# game_console_schematic.net
KiCad netlist of a schematic drawn in Altium Designer
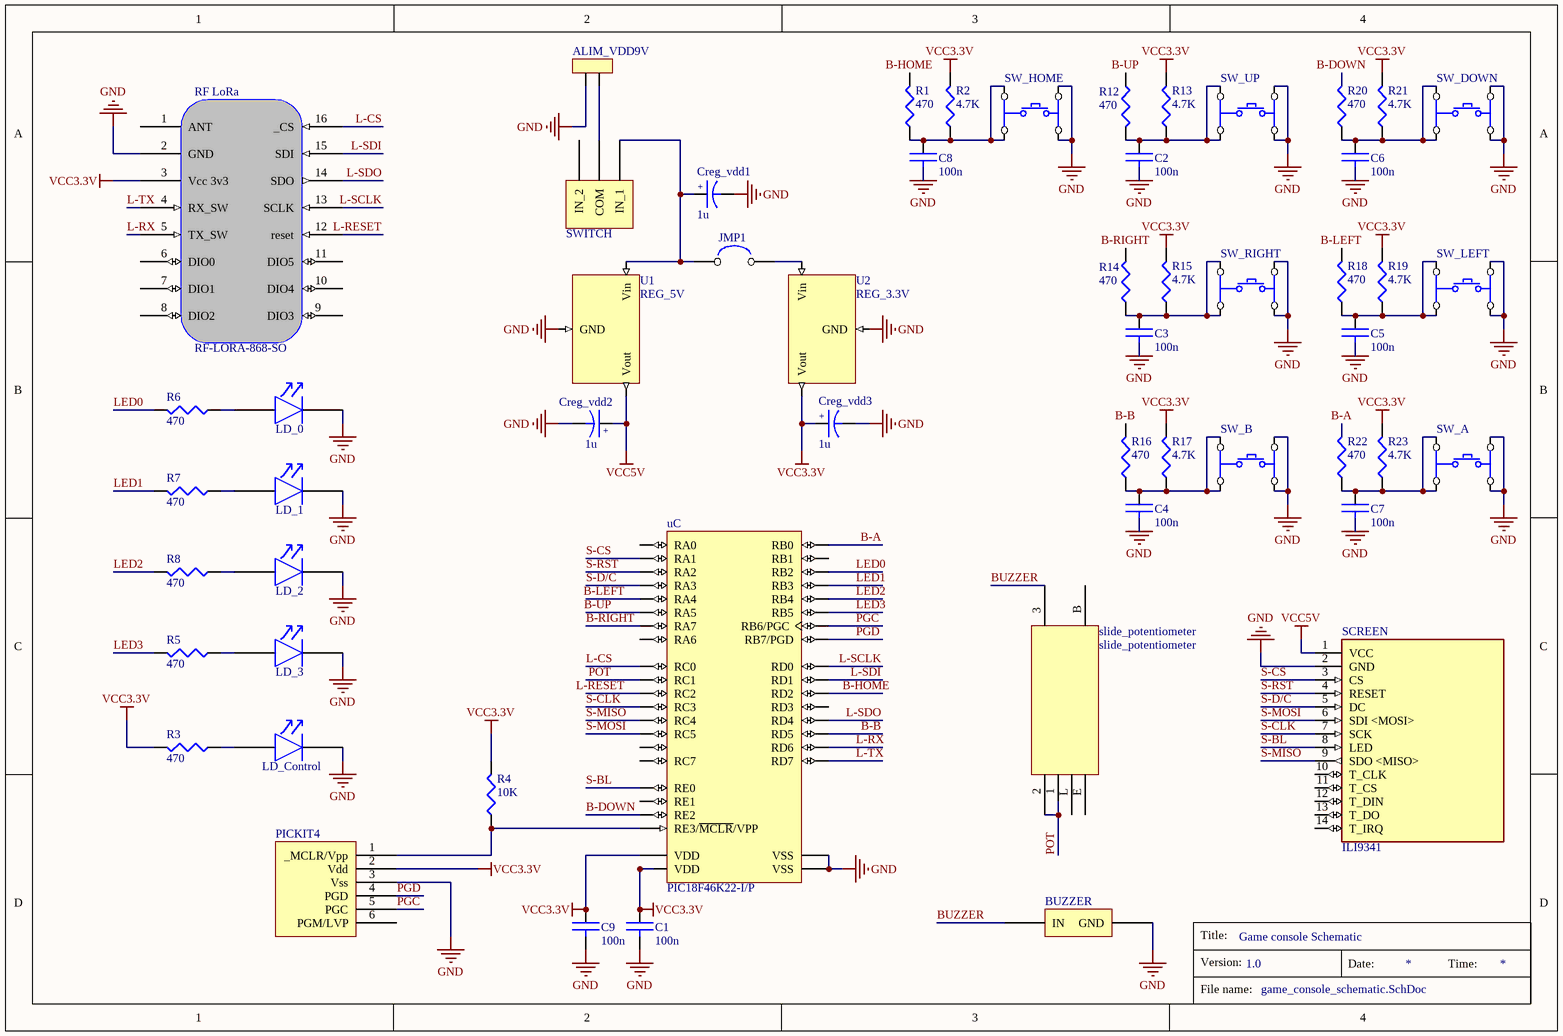
[diagram p0: game_console_schematic.SchDoc]

(export (version "E")
  (design (tool "Eeschema 10.0.6"))
  (components
    (comp (ref "ALIM_VDD9V")
      (value "ALIM_9V")
      (footprint "AMP_2")
      (description "connecteur alim 2 pôles")
      (libsource (lib "power2") (part "POWER2"))
    )
    (comp (ref "BUZZER") (value "BUZZER") (footprint "BUZZER") (libsource (lib "buzzer") (part "BUZZER")))
    (comp (ref "C1")
      (value "100n")
      (footprint "0805")
      (description "capacité non polarisée")
      (fields (field (name "Comment") "CAP"))
      (libsource (lib "ISEN_basics_15-02-2023") (part "CAP"))
    )
    (comp (ref "C2")
      (value "100n")
      (footprint "0805")
      (description "capacité non polarisée")
      (fields (field (name "Comment") "C"))
      (libsource (lib "ISEN_basics_15-02-2023") (part "CAP"))
    )
    (comp (ref "C3")
      (value "100n")
      (footprint "0805")
      (description "capacité non polarisée")
      (fields (field (name "Comment") "C"))
      (libsource (lib "ISEN_basics_15-02-2023") (part "CAP"))
    )
    (comp (ref "C4")
      (value "100n")
      (footprint "0805")
      (description "capacité non polarisée")
      (fields (field (name "Comment") "C"))
      (libsource (lib "ISEN_basics_15-02-2023") (part "CAP"))
    )
    (comp (ref "C5")
      (value "100n")
      (footprint "0805")
      (description "capacité non polarisée")
      (fields (field (name "Comment") "C"))
      (libsource (lib "ISEN_basics_15-02-2023") (part "CAP"))
    )
    (comp (ref "C6")
      (value "100n")
      (footprint "0805")
      (description "capacité non polarisée")
      (fields (field (name "Comment") "C"))
      (libsource (lib "ISEN_basics_15-02-2023") (part "CAP"))
    )
    (comp (ref "C7")
      (value "100n")
      (footprint "0805")
      (description "capacité non polarisée")
      (fields (field (name "Comment") "C"))
      (libsource (lib "ISEN_basics_15-02-2023") (part "CAP"))
    )
    (comp (ref "C8")
      (value "100n")
      (footprint "0805")
      (description "capacité non polarisée")
      (fields (field (name "Comment") "C"))
      (libsource (lib "ISEN_basics_15-02-2023") (part "CAP"))
    )
    (comp (ref "C9")
      (value "100n")
      (footprint "0805")
      (description "capacité non polarisée")
      (fields (field (name "Comment") "CAP"))
      (libsource (lib "ISEN_basics_15-02-2023") (part "CAP"))
    )
    (comp (ref "Creg_vdd1")
      (value "1u")
      (footprint "RB.2/.4")
      (description "capacité polarisée")
      (fields (field (name "Comment") "CAP_POL"))
      (libsource (lib "condensateur_pol") (part "CAP_POL"))
    )
    (comp (ref "Creg_vdd2")
      (value "1u")
      (footprint "RB.2/.4")
      (description "capacité polarisée")
      (fields (field (name "Comment") "CAP_POL"))
      (libsource (lib "condensateur_pol") (part "CAP_POL"))
    )
    (comp (ref "Creg_vdd3")
      (value "1u")
      (footprint "RB.2/.4")
      (description "capacité polarisée")
      (fields (field (name "Comment") "CAP_POL"))
      (libsource (lib "condensateur_pol") (part "CAP_POL"))
    )
    (comp (ref "JMP1")
      (value "JUMPER")
      (footprint "JMP2-100")
      (description "cavalier 1 position")
      (libsource (lib "jumper2") (part "JUMPER2"))
    )
    (comp (ref "LD_0")
      (value "0")
      (footprint "LED0805")
      (description "LED 5mm/3mm/CMS")
      (libsource (lib "led") (part "LED"))
    )
    (comp (ref "LD_1")
      (value "1")
      (footprint "LED0805")
      (description "LED 5mm/3mm/CMS")
      (libsource (lib "led") (part "LED"))
    )
    (comp (ref "LD_2")
      (value "2")
      (footprint "LED0805")
      (description "LED 5mm/3mm/CMS")
      (libsource (lib "led") (part "LED"))
    )
    (comp (ref "LD_3")
      (value "3")
      (footprint "LED0805")
      (description "LED 5mm/3mm/CMS")
      (libsource (lib "led") (part "LED"))
    )
    (comp (ref "LD_Control")
      (value "comment")
      (footprint "LED0805")
      (description "LED 5mm/3mm/CMS")
      (libsource (lib "led") (part "LED"))
    )
    (comp (ref "PICKIT4")
      (value "PIC-ICSP")
      (footprint "PIC-ICSP")
      (libsource (lib "pickit4-connection") (part "PIC-ICSP"))
    )
    (comp (ref "R1")
      (value "470")
      (footprint "0805")
      (description "resistance")
      (fields (field (name "Comment") "R0"))
      (libsource (lib "ISEN_basics_15-02-2023") (part "RES"))
    )
    (comp (ref "R2")
      (value "4.7K")
      (footprint "0805")
      (description "resistance")
      (fields (field (name "Comment") "RK"))
      (libsource (lib "ISEN_basics_15-02-2023") (part "RES"))
    )
    (comp (ref "R3")
      (value "470")
      (footprint "0805")
      (description "resistance")
      (fields (field (name "Comment") "R0"))
      (libsource (lib "ISEN_basics_15-02-2023") (part "RES"))
    )
    (comp (ref "R4")
      (value "10K")
      (footprint "0805")
      (description "resistance")
      (fields (field (name "Comment") "RES"))
      (libsource (lib "ISEN_basics_15-02-2023") (part "RES"))
    )
    (comp (ref "R5")
      (value "470")
      (footprint "0805")
      (description "resistance")
      (fields (field (name "Comment") "R0"))
      (libsource (lib "ISEN_basics_15-02-2023") (part "RES"))
    )
    (comp (ref "R6")
      (value "470")
      (footprint "0805")
      (description "resistance")
      (fields (field (name "Comment") "R0"))
      (libsource (lib "ISEN_basics_15-02-2023") (part "RES"))
    )
    (comp (ref "R7")
      (value "470")
      (footprint "0805")
      (description "resistance")
      (fields (field (name "Comment") "R0"))
      (libsource (lib "ISEN_basics_15-02-2023") (part "RES"))
    )
    (comp (ref "R8")
      (value "470")
      (footprint "0805")
      (description "resistance")
      (fields (field (name "Comment") "R0"))
      (libsource (lib "ISEN_basics_15-02-2023") (part "RES"))
    )
    (comp (ref "R12")
      (value "470")
      (footprint "0805")
      (description "resistance")
      (fields (field (name "Comment") "R0"))
      (libsource (lib "ISEN_basics_15-02-2023") (part "RES"))
    )
    (comp (ref "R13")
      (value "4.7K")
      (footprint "0805")
      (description "resistance")
      (fields (field (name "Comment") "RK"))
      (libsource (lib "ISEN_basics_15-02-2023") (part "RES"))
    )
    (comp (ref "R14")
      (value "470")
      (footprint "0805")
      (description "resistance")
      (fields (field (name "Comment") "R0"))
      (libsource (lib "ISEN_basics_15-02-2023") (part "RES"))
    )
    (comp (ref "R15")
      (value "4.7K")
      (footprint "0805")
      (description "resistance")
      (fields (field (name "Comment") "RK"))
      (libsource (lib "ISEN_basics_15-02-2023") (part "RES"))
    )
    (comp (ref "R16")
      (value "470")
      (footprint "0805")
      (description "resistance")
      (fields (field (name "Comment") "R0"))
      (libsource (lib "ISEN_basics_15-02-2023") (part "RES"))
    )
    (comp (ref "R17")
      (value "4.7K")
      (footprint "0805")
      (description "resistance")
      (fields (field (name "Comment") "RK"))
      (libsource (lib "ISEN_basics_15-02-2023") (part "RES"))
    )
    (comp (ref "R18")
      (value "470")
      (footprint "0805")
      (description "resistance")
      (fields (field (name "Comment") "R0"))
      (libsource (lib "ISEN_basics_15-02-2023") (part "RES"))
    )
    (comp (ref "R19")
      (value "4.7K")
      (footprint "0805")
      (description "resistance")
      (fields (field (name "Comment") "RK"))
      (libsource (lib "ISEN_basics_15-02-2023") (part "RES"))
    )
    (comp (ref "R20")
      (value "470")
      (footprint "0805")
      (description "resistance")
      (fields (field (name "Comment") "R0"))
      (libsource (lib "ISEN_basics_15-02-2023") (part "RES"))
    )
    (comp (ref "R21")
      (value "4.7K")
      (footprint "0805")
      (description "resistance")
      (fields (field (name "Comment") "RK"))
      (libsource (lib "ISEN_basics_15-02-2023") (part "RES"))
    )
    (comp (ref "R22")
      (value "470")
      (footprint "0805")
      (description "resistance")
      (fields (field (name "Comment") "R0"))
      (libsource (lib "ISEN_basics_15-02-2023") (part "RES"))
    )
    (comp (ref "R23")
      (value "4.7K")
      (footprint "0805")
      (description "resistance")
      (fields (field (name "Comment") "RK"))
      (libsource (lib "ISEN_basics_15-02-2023") (part "RES"))
    )
    (comp (ref "RF LoRa")
      (value "RF-LORA-868-SO")
      (footprint "RF-LORA-868-DIP")
      (libsource (lib "rf-lora") (part "RF-LORA-868-SO"))
    )
    (comp (ref "SCREEN")
      (value "ILI9341")
      (footprint "ILI9341_Display")
      (fields (field (name "MF") "Adafruit Industries") (field (name "MP") "2478"))
      (libsource (lib "ILI9341_Display") (part "2478"))
    )
    (comp (ref "slide_potentiometer")
      (value "slide_potentiometer")
      (footprint "ptl_series_slide_potentiometer")
      (libsource (lib "slide_potentiometer") (part "slide_potentiometer"))
    )
    (comp (ref "SWITCH")
      (value "SWITCH_SPDT_ON_ON_2")
      (footprint "SW_MFP-161")
      (libsource (lib "commutateur") (part "SWITCH_SPDT_ON_ON_2"))
    )
    (comp (ref "SW_A") (value "A") (footprint "KSA") (libsource (lib "custom_push_button") (part "SW_PB")))
    (comp (ref "SW_B") (value "B") (footprint "KSA") (libsource (lib "custom_push_button") (part "SW_PB")))
    (comp (ref "SW_DOWN")
      (value "SW_PB")
      (footprint "KSA")
      (libsource (lib "custom_push_button") (part "SW_PB"))
    )
    (comp (ref "SW_HOME")
      (value "HOME")
      (footprint "KSA")
      (libsource (lib "custom_push_button") (part "SW_PB"))
    )
    (comp (ref "SW_LEFT")
      (value "SW_PB")
      (footprint "KSA")
      (libsource (lib "custom_push_button") (part "SW_PB"))
    )
    (comp (ref "SW_RIGHT")
      (value "SW_PB")
      (footprint "KSA")
      (libsource (lib "custom_push_button") (part "SW_PB"))
    )
    (comp (ref "SW_UP")
      (value "SW_PB")
      (footprint "KSA")
      (libsource (lib "custom_push_button") (part "SW_PB"))
    )
    (comp (ref "U1")
      (value "REG_5V")
      (footprint "TO220H")
      (description "régulateur positif fixe")
      (libsource (lib "regulateur") (part "REG_POS"))
    )
    (comp (ref "U2")
      (value "REG_3.3V")
      (footprint "TO220H")
      (description "régulateur positif fixe")
      (libsource (lib "") (part "REG_POS_1"))
    )
    (comp (ref "uC")
      (value "PIC18F46K22-I/P")
      (footprint "MCHP-PDIP-P40")
      (fields (field (name "MANUFACTURER") "Microchip"))
      (libsource (lib "Microchip PIC18") (part "PIC18F46K22-I/P"))
    )
  )
  (nets
    (net (code "1") (name "/B-A") (class "Default")
      (node (ref "R22") (pin "2") (pintype "passive"))
      (node (ref "uC") (pin "33") (pinfunction "RB0_33") (pintype "bidirectional"))
    )
    (net (code "2") (name "/B-B") (class "Default")
      (node (ref "R16") (pin "2") (pintype "passive"))
      (node (ref "uC") (pin "28") (pinfunction "RD5_28") (pintype "bidirectional"))
    )
    (net (code "3") (name "/B-DOWN") (class "Default")
      (node (ref "R20") (pin "2") (pintype "passive"))
      (node (ref "uC") (pin "10") (pinfunction "RE2_10") (pintype "bidirectional"))
    )
    (net (code "4") (name "/B-HOME") (class "Default")
      (node (ref "R1") (pin "2") (pintype "passive"))
      (node (ref "uC") (pin "21") (pinfunction "RD2_21") (pintype "bidirectional"))
    )
    (net (code "5") (name "/B-LEFT") (class "Default")
      (node (ref "R18") (pin "2") (pintype "passive"))
      (node (ref "uC") (pin "6") (pinfunction "RA4_6") (pintype "bidirectional"))
    )
    (net (code "6") (name "/B-RIGHT") (class "Default")
      (node (ref "R14") (pin "2") (pintype "passive"))
      (node (ref "uC") (pin "13") (pinfunction "RA7_13") (pintype "bidirectional"))
    )
    (net (code "7") (name "/B-UP") (class "Default")
      (node (ref "R12") (pin "1") (pintype "passive"))
      (node (ref "uC") (pin "7") (pinfunction "RA5_7") (pintype "bidirectional"))
    )
    (net (code "8") (name "/BUZZER") (class "Default")
      (node (ref "BUZZER") (pin "1") (pinfunction "IN_1") (pintype "passive"))
      (node (ref "slide_potentiometer") (pin "3") (pintype "passive"))
    )
    (net (code "9") (name "/L-CS") (class "Default")
      (node (ref "RF LoRa") (pin "16") (pinfunction "_CS_16") (pintype "input"))
      (node (ref "uC") (pin "15") (pinfunction "RC0_15") (pintype "bidirectional"))
    )
    (net (code "10") (name "/L-RESET") (class "Default")
      (node (ref "RF LoRa") (pin "12") (pinfunction "reset_12") (pintype "input"))
      (node (ref "uC") (pin "17") (pinfunction "RC2_17") (pintype "bidirectional"))
    )
    (net (code "11") (name "/L-RX") (class "Default")
      (node (ref "RF LoRa") (pin "5") (pinfunction "TX_SW_5") (pintype "input"))
      (node (ref "uC") (pin "29") (pinfunction "RD6_29") (pintype "bidirectional"))
    )
    (net (code "12") (name "/L-SCLK") (class "Default")
      (node (ref "RF LoRa") (pin "13") (pinfunction "SCLK_13") (pintype "input"))
      (node (ref "uC") (pin "19") (pinfunction "RD0_19") (pintype "bidirectional"))
    )
    (net (code "13") (name "/L-SDI") (class "Default")
      (node (ref "RF LoRa") (pin "15") (pinfunction "SDI_15") (pintype "input"))
      (node (ref "uC") (pin "20") (pinfunction "RD1_20") (pintype "bidirectional"))
    )
    (net (code "14") (name "/L-SDO") (class "Default")
      (node (ref "RF LoRa") (pin "14") (pinfunction "SDO_14") (pintype "output"))
      (node (ref "uC") (pin "27") (pinfunction "RD4_27") (pintype "bidirectional"))
    )
    (net (code "15") (name "/L-TX") (class "Default")
      (node (ref "RF LoRa") (pin "4") (pinfunction "RX_SW_4") (pintype "input"))
      (node (ref "uC") (pin "30") (pinfunction "RD7_30") (pintype "bidirectional"))
    )
    (net (code "16") (name "/LED0") (class "Default")
      (node (ref "R6") (pin "2") (pintype "passive"))
      (node (ref "uC") (pin "35") (pinfunction "RB2_35") (pintype "bidirectional"))
    )
    (net (code "17") (name "/LED1") (class "Default")
      (node (ref "R7") (pin "2") (pintype "passive"))
      (node (ref "uC") (pin "36") (pinfunction "RB3_36") (pintype "bidirectional"))
    )
    (net (code "18") (name "/LED2") (class "Default")
      (node (ref "R8") (pin "2") (pintype "passive"))
      (node (ref "uC") (pin "37") (pinfunction "RB4_37") (pintype "bidirectional"))
    )
    (net (code "19") (name "/LED3") (class "Default")
      (node (ref "R5") (pin "2") (pintype "passive"))
      (node (ref "uC") (pin "38") (pinfunction "RB5_38") (pintype "bidirectional"))
    )
    (net (code "20") (name "/PGC") (class "Default")
      (node (ref "PICKIT4") (pin "5") (pinfunction "PGC_5") (pintype "passive"))
      (node (ref "uC") (pin "39") (pinfunction "RB6/PGC_39") (pintype "bidirectional"))
    )
    (net (code "21") (name "/PGD") (class "Default")
      (node (ref "PICKIT4") (pin "4") (pinfunction "PGD_4") (pintype "passive"))
      (node (ref "uC") (pin "40") (pinfunction "RB7/PGD_40") (pintype "bidirectional"))
    )
    (net (code "22") (name "/POT") (class "Default")
      (node (ref "slide_potentiometer") (pin "1") (pintype "passive"))
      (node (ref "slide_potentiometer") (pin "2") (pintype "passive"))
      (node (ref "uC") (pin "16") (pinfunction "RC1_16") (pintype "bidirectional"))
    )
    (net (code "23") (name "/S-BL") (class "Default")
      (node (ref "SCREEN") (pin "8") (pinfunction "LED_8") (pintype "input"))
      (node (ref "uC") (pin "8") (pinfunction "RE0_8") (pintype "bidirectional"))
    )
    (net (code "24") (name "/S-CLK") (class "Default")
      (node (ref "SCREEN") (pin "7") (pinfunction "SCK_7") (pintype "input"))
      (node (ref "uC") (pin "18") (pinfunction "RC3_18") (pintype "bidirectional"))
    )
    (net (code "25") (name "/S-CS") (class "Default")
      (node (ref "SCREEN") (pin "3") (pinfunction "CS_3") (pintype "input"))
      (node (ref "uC") (pin "3") (pinfunction "RA1_3") (pintype "bidirectional"))
    )
    (net (code "26") (name "/S-D{slash}C") (class "Default")
      (node (ref "SCREEN") (pin "5") (pinfunction "DC_5") (pintype "input"))
      (node (ref "uC") (pin "5") (pinfunction "RA3_5") (pintype "bidirectional"))
    )
    (net (code "27") (name "/S-MISO") (class "Default")
      (node (ref "SCREEN") (pin "9") (pinfunction "SDO_<MISO>_9") (pintype "output"))
      (node (ref "uC") (pin "23") (pinfunction "RC4_23") (pintype "bidirectional"))
    )
    (net (code "28") (name "/S-MOSI") (class "Default")
      (node (ref "SCREEN") (pin "6") (pinfunction "SDI_<MOSI>_6") (pintype "input"))
      (node (ref "uC") (pin "24") (pinfunction "RC5_24") (pintype "bidirectional"))
    )
    (net (code "29") (name "/S-RST") (class "Default")
      (node (ref "SCREEN") (pin "4") (pinfunction "RESET_4") (pintype "input"))
      (node (ref "uC") (pin "4") (pinfunction "RA2_4") (pintype "bidirectional"))
    )
    (net (code "30") (name "GND") (class "Default")
      (node (ref "ALIM_VDD9V") (pin "2") (pintype "passive"))
      (node (ref "BUZZER") (pin "2") (pinfunction "GND_2") (pintype "passive"))
      (node (ref "C1") (pin "2") (pinfunction "2_2") (pintype "passive"))
      (node (ref "C2") (pin "2") (pinfunction "2_2") (pintype "passive"))
      (node (ref "C3") (pin "2") (pinfunction "2_2") (pintype "passive"))
      (node (ref "C4") (pin "2") (pinfunction "2_2") (pintype "passive"))
      (node (ref "C5") (pin "2") (pinfunction "2_2") (pintype "passive"))
      (node (ref "C6") (pin "2") (pinfunction "2_2") (pintype "passive"))
      (node (ref "C7") (pin "2") (pinfunction "2_2") (pintype "passive"))
      (node (ref "C8") (pin "2") (pinfunction "2_2") (pintype "passive"))
      (node (ref "C9") (pin "2") (pinfunction "2_2") (pintype "passive"))
      (node (ref "Creg_vdd1") (pin "2") (pinfunction "2_2") (pintype "passive"))
      (node (ref "Creg_vdd2") (pin "2") (pinfunction "2_2") (pintype "passive"))
      (node (ref "Creg_vdd3") (pin "2") (pinfunction "2_2") (pintype "passive"))
      (node (ref "LD_0") (pin "K") (pinfunction "10_K") (pintype "passive"))
      (node (ref "LD_1") (pin "K") (pinfunction "10_K") (pintype "passive"))
      (node (ref "LD_2") (pin "K") (pinfunction "10_K") (pintype "passive"))
      (node (ref "LD_3") (pin "K") (pinfunction "10_K") (pintype "passive"))
      (node (ref "LD_Control") (pin "K") (pinfunction "10_K") (pintype "passive"))
      (node (ref "PICKIT4") (pin "3") (pinfunction "Vss_3") (pintype "passive"))
      (node (ref "RF LoRa") (pin "2") (pinfunction "GND_2") (pintype "power_in"))
      (node (ref "SCREEN") (pin "2") (pinfunction "GND_2") (pintype "power_in"))
      (node (ref "SW_A") (pin "3") (pintype "passive"))
      (node (ref "SW_A") (pin "4") (pintype "passive"))
      (node (ref "SW_B") (pin "3") (pintype "passive"))
      (node (ref "SW_B") (pin "4") (pintype "passive"))
      (node (ref "SW_DOWN") (pin "3") (pintype "passive"))
      (node (ref "SW_DOWN") (pin "4") (pintype "passive"))
      (node (ref "SW_HOME") (pin "3") (pintype "passive"))
      (node (ref "SW_HOME") (pin "4") (pintype "passive"))
      (node (ref "SW_LEFT") (pin "3") (pintype "passive"))
      (node (ref "SW_LEFT") (pin "4") (pintype "passive"))
      (node (ref "SW_RIGHT") (pin "3") (pintype "passive"))
      (node (ref "SW_RIGHT") (pin "4") (pintype "passive"))
      (node (ref "SW_UP") (pin "3") (pintype "passive"))
      (node (ref "SW_UP") (pin "4") (pintype "passive"))
      (node (ref "U1") (pin "2") (pinfunction "GND_2") (pintype "input"))
      (node (ref "U2") (pin "2") (pinfunction "GND_2") (pintype "input"))
      (node (ref "uC") (pin "12") (pinfunction "VSS_12") (pintype "power_in"))
      (node (ref "uC") (pin "31") (pinfunction "VSS_31") (pintype "power_in"))
    )
    (net (code "31") (name "Net-(C2-Pad1)") (class "Default")
      (node (ref "C2") (pin "1") (pinfunction "1_1") (pintype "passive"))
      (node (ref "R12") (pin "2") (pintype "passive"))
      (node (ref "R13") (pin "1") (pintype "passive"))
      (node (ref "SW_UP") (pin "1") (pintype "passive"))
      (node (ref "SW_UP") (pin "2") (pintype "passive"))
    )
    (net (code "32") (name "Net-(C3-Pad1)") (class "Default")
      (node (ref "C3") (pin "1") (pinfunction "1_1") (pintype "passive"))
      (node (ref "R14") (pin "1") (pintype "passive"))
      (node (ref "R15") (pin "1") (pintype "passive"))
      (node (ref "SW_RIGHT") (pin "1") (pintype "passive"))
      (node (ref "SW_RIGHT") (pin "2") (pintype "passive"))
    )
    (net (code "33") (name "Net-(C4-Pad1)") (class "Default")
      (node (ref "C4") (pin "1") (pinfunction "1_1") (pintype "passive"))
      (node (ref "R16") (pin "1") (pintype "passive"))
      (node (ref "R17") (pin "1") (pintype "passive"))
      (node (ref "SW_B") (pin "1") (pintype "passive"))
      (node (ref "SW_B") (pin "2") (pintype "passive"))
    )
    (net (code "34") (name "Net-(C5-Pad1)") (class "Default")
      (node (ref "C5") (pin "1") (pinfunction "1_1") (pintype "passive"))
      (node (ref "R18") (pin "1") (pintype "passive"))
      (node (ref "R19") (pin "1") (pintype "passive"))
      (node (ref "SW_LEFT") (pin "1") (pintype "passive"))
      (node (ref "SW_LEFT") (pin "2") (pintype "passive"))
    )
    (net (code "35") (name "Net-(C6-Pad1)") (class "Default")
      (node (ref "C6") (pin "1") (pinfunction "1_1") (pintype "passive"))
      (node (ref "R20") (pin "1") (pintype "passive"))
      (node (ref "R21") (pin "1") (pintype "passive"))
      (node (ref "SW_DOWN") (pin "1") (pintype "passive"))
      (node (ref "SW_DOWN") (pin "2") (pintype "passive"))
    )
    (net (code "36") (name "Net-(C7-Pad1)") (class "Default")
      (node (ref "C7") (pin "1") (pinfunction "1_1") (pintype "passive"))
      (node (ref "R22") (pin "1") (pintype "passive"))
      (node (ref "R23") (pin "1") (pintype "passive"))
      (node (ref "SW_A") (pin "1") (pintype "passive"))
      (node (ref "SW_A") (pin "2") (pintype "passive"))
    )
    (net (code "37") (name "Net-(C8-Pad1)") (class "Default")
      (node (ref "C8") (pin "1") (pinfunction "1_1") (pintype "passive"))
      (node (ref "R1") (pin "1") (pintype "passive"))
      (node (ref "R2") (pin "1") (pintype "passive"))
      (node (ref "SW_HOME") (pin "1") (pintype "passive"))
      (node (ref "SW_HOME") (pin "2") (pintype "passive"))
    )
    (net (code "38") (name "Net-(LD_0-8)") (class "Default")
      (node (ref "LD_0") (pin "A") (pinfunction "8_A") (pintype "passive"))
      (node (ref "R6") (pin "1") (pintype "passive"))
    )
    (net (code "39") (name "Net-(LD_1-8)") (class "Default")
      (node (ref "LD_1") (pin "A") (pinfunction "8_A") (pintype "passive"))
      (node (ref "R7") (pin "1") (pintype "passive"))
    )
    (net (code "40") (name "Net-(LD_2-8)") (class "Default")
      (node (ref "LD_2") (pin "A") (pinfunction "8_A") (pintype "passive"))
      (node (ref "R8") (pin "1") (pintype "passive"))
    )
    (net (code "41") (name "Net-(LD_3-8)") (class "Default")
      (node (ref "LD_3") (pin "A") (pinfunction "8_A") (pintype "passive"))
      (node (ref "R5") (pin "1") (pintype "passive"))
    )
    (net (code "42") (name "Net-(LD_Control-8)") (class "Default")
      (node (ref "LD_Control") (pin "A") (pinfunction "8_A") (pintype "passive"))
      (node (ref "R3") (pin "1") (pintype "passive"))
    )
    (net (code "43") (name "Net-(PICKIT4-_MCLR{slash}Vpp)") (class "Default")
      (node (ref "PICKIT4") (pin "1") (pinfunction "_MCLR/Vpp_1") (pintype "passive"))
      (node (ref "R4") (pin "1") (pintype "passive"))
      (node (ref "uC") (pin "1") (pinfunction "RE3/~{MCLR}/VPP_1") (pintype "input"))
    )
    (net (code "44") (name "Net-(SWITCH-COM)") (class "Default")
      (node (ref "ALIM_VDD9V") (pin "1") (pintype "passive"))
      (node (ref "SWITCH") (pin "2") (pinfunction "COM_2") (pintype "passive"))
    )
    (net (code "45") (name "Net-(SWITCH-IN_1)") (class "Default")
      (node (ref "Creg_vdd1") (pin "1") (pinfunction "1_1") (pintype "passive"))
      (node (ref "JMP1") (pin "1") (pintype "passive"))
      (node (ref "SWITCH") (pin "1") (pinfunction "IN_1_1") (pintype "passive"))
      (node (ref "U1") (pin "1") (pinfunction "Vin_1") (pintype "input"))
    )
    (net (code "46") (name "Net-(U2-Vin)") (class "Default")
      (node (ref "JMP1") (pin "2") (pintype "passive"))
      (node (ref "U2") (pin "1") (pinfunction "Vin_1") (pintype "input"))
    )
    (net (code "47") (name "VCC3.3V") (class "Default")
      (node (ref "C1") (pin "1") (pinfunction "1_1") (pintype "passive"))
      (node (ref "C9") (pin "1") (pinfunction "1_1") (pintype "passive"))
      (node (ref "Creg_vdd3") (pin "1") (pinfunction "1_1") (pintype "passive"))
      (node (ref "PICKIT4") (pin "2") (pinfunction "Vdd_2") (pintype "passive"))
      (node (ref "R13") (pin "2") (pintype "passive"))
      (node (ref "R15") (pin "2") (pintype "passive"))
      (node (ref "R17") (pin "2") (pintype "passive"))
      (node (ref "R19") (pin "2") (pintype "passive"))
      (node (ref "R2") (pin "2") (pintype "passive"))
      (node (ref "R21") (pin "2") (pintype "passive"))
      (node (ref "R23") (pin "2") (pintype "passive"))
      (node (ref "R3") (pin "2") (pintype "passive"))
      (node (ref "R4") (pin "2") (pintype "passive"))
      (node (ref "RF LoRa") (pin "3") (pinfunction "Vcc_3v3_3") (pintype "power_in"))
      (node (ref "U2") (pin "3") (pinfunction "Vout_3") (pintype "output"))
      (node (ref "uC") (pin "11") (pinfunction "VDD_11") (pintype "power_in"))
      (node (ref "uC") (pin "32") (pinfunction "VDD_32") (pintype "power_in"))
    )
    (net (code "48") (name "VCC5V") (class "Default")
      (node (ref "Creg_vdd2") (pin "1") (pinfunction "1_1") (pintype "passive"))
      (node (ref "SCREEN") (pin "1") (pinfunction "VCC_1") (pintype "power_in"))
      (node (ref "U1") (pin "3") (pinfunction "Vout_3") (pintype "output"))
    )
    (net (code "49") (name "unconnected-(PICKIT4-PGM{slash}LVP-Pad6)") (class "Default")
      (node (ref "PICKIT4") (pin "6") (pinfunction "PGM/LVP_6") (pintype "passive"))
    )
    (net (code "50") (name "unconnected-(RF LoRa-ANT-Pad1)") (class "Default")
      (node (ref "RF LoRa") (pin "1") (pinfunction "ANT_1") (pintype "passive"))
    )
    (net (code "51") (name "unconnected-(RF LoRa-DIO0-Pad6)") (class "Default")
      (node (ref "RF LoRa") (pin "6") (pinfunction "DIO0_6") (pintype "bidirectional"))
    )
    (net (code "52") (name "unconnected-(RF LoRa-DIO1-Pad7)") (class "Default")
      (node (ref "RF LoRa") (pin "7") (pinfunction "DIO1_7") (pintype "bidirectional"))
    )
    (net (code "53") (name "unconnected-(RF LoRa-DIO2-Pad8)") (class "Default")
      (node (ref "RF LoRa") (pin "8") (pinfunction "DIO2_8") (pintype "bidirectional"))
    )
    (net (code "54") (name "unconnected-(RF LoRa-DIO3-Pad9)") (class "Default")
      (node (ref "RF LoRa") (pin "9") (pinfunction "DIO3_9") (pintype "bidirectional"))
    )
    (net (code "55") (name "unconnected-(RF LoRa-DIO4-Pad10)") (class "Default")
      (node (ref "RF LoRa") (pin "10") (pinfunction "DIO4_10") (pintype "bidirectional"))
    )
    (net (code "56") (name "unconnected-(RF LoRa-DIO5-Pad11)") (class "Default")
      (node (ref "RF LoRa") (pin "11") (pinfunction "DIO5_11") (pintype "bidirectional"))
    )
    (net (code "57") (name "unconnected-(SCREEN-T_CLK-Pad10)") (class "Default")
      (node (ref "SCREEN") (pin "10") (pinfunction "T_CLK_10") (pintype "bidirectional"))
    )
    (net (code "58") (name "unconnected-(SCREEN-T_CS-Pad11)") (class "Default")
      (node (ref "SCREEN") (pin "11") (pinfunction "T_CS_11") (pintype "bidirectional"))
    )
    (net (code "59") (name "unconnected-(SCREEN-T_DIN-Pad12)") (class "Default")
      (node (ref "SCREEN") (pin "12") (pinfunction "T_DIN_12") (pintype "bidirectional"))
    )
    (net (code "60") (name "unconnected-(SCREEN-T_DO-Pad13)") (class "Default")
      (node (ref "SCREEN") (pin "13") (pinfunction "T_DO_13") (pintype "bidirectional"))
    )
    (net (code "61") (name "unconnected-(SCREEN-T_IRQ-Pad14)") (class "Default")
      (node (ref "SCREEN") (pin "14") (pinfunction "T_IRQ_14") (pintype "bidirectional"))
    )
    (net (code "62") (name "unconnected-(SWITCH-IN_2-Pad3)") (class "Default")
      (node (ref "SWITCH") (pin "3") (pinfunction "IN_2_3") (pintype "passive"))
    )
    (net (code "63") (name "unconnected-(slide_potentiometer-PadB)") (class "Default")
      (node (ref "slide_potentiometer") (pin "B") (pintype "power_in"))
    )
    (net (code "64") (name "unconnected-(slide_potentiometer-PadE)") (class "Default")
      (node (ref "slide_potentiometer") (pin "E") (pintype "passive"))
    )
    (net (code "65") (name "unconnected-(slide_potentiometer-PadL)") (class "Default")
      (node (ref "slide_potentiometer") (pin "L") (pintype "passive"))
    )
    (net (code "66") (name "unconnected-(uC-RA0-Pad2)") (class "Default")
      (node (ref "uC") (pin "2") (pinfunction "RA0_2") (pintype "bidirectional"))
    )
    (net (code "67") (name "unconnected-(uC-RA6-Pad14)") (class "Default")
      (node (ref "uC") (pin "14") (pinfunction "RA6_14") (pintype "bidirectional"))
    )
    (net (code "68") (name "unconnected-(uC-RB1-Pad34)") (class "Default")
      (node (ref "uC") (pin "34") (pinfunction "RB1_34") (pintype "bidirectional"))
    )
    (net (code "69") (name "unconnected-(uC-RC6-Pad25)") (class "Default")
      (node (ref "uC") (pin "25") (pinfunction "RC6_25") (pintype "bidirectional"))
    )
    (net (code "70") (name "unconnected-(uC-RC7-Pad26)") (class "Default")
      (node (ref "uC") (pin "26") (pinfunction "RC7_26") (pintype "bidirectional"))
    )
    (net (code "71") (name "unconnected-(uC-RD3-Pad22)") (class "Default")
      (node (ref "uC") (pin "22") (pinfunction "RD3_22") (pintype "bidirectional"))
    )
    (net (code "72") (name "unconnected-(uC-RE1-Pad9)") (class "Default")
      (node (ref "uC") (pin "9") (pinfunction "RE1_9") (pintype "bidirectional"))
    )
  )
)
